# TTGO-TS-dash-display.net
KiCad netlist of a schematic drawn in EAGLE
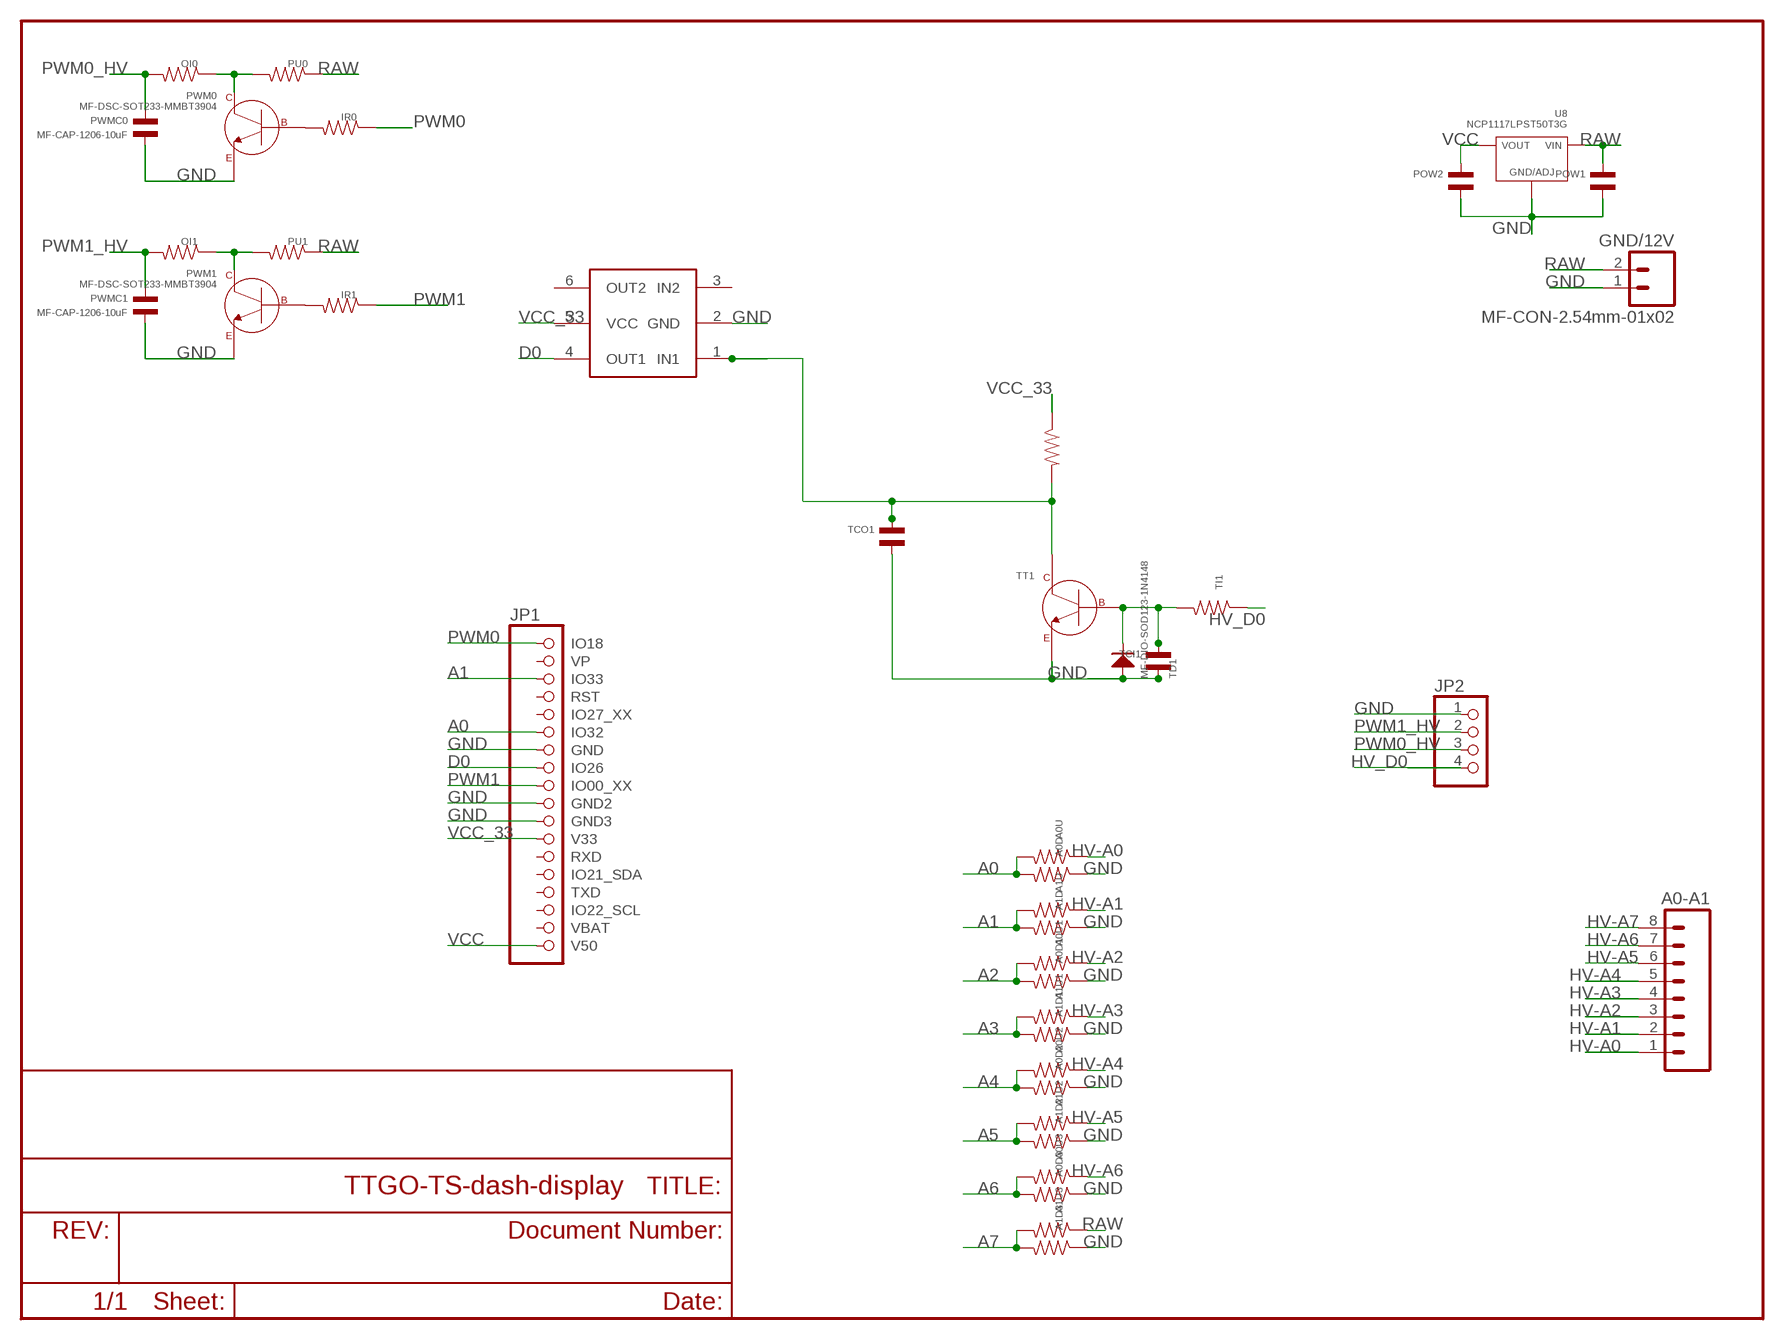
[diagram p0: schematic, sheet 1]

(export (version "E")
  (design (tool "Eeschema 10.0.6"))
  (components
    (comp (ref "A0-A1")
      (value "MF-CON-2.54mm-01x08")
      (footprint "eagle-import:1X08")
      (libsource (lib "eagle-import") (part "M081X08"))
    )
    (comp (ref "A0D")
      (value "RESISTOR_1206")
      (footprint "eagle-import:R1206")
      (libsource (lib "eagle-import") (part "RESISTOR_1206"))
    )
    (comp (ref "A0D1")
      (value "RESISTOR_1206")
      (footprint "eagle-import:R1206")
      (libsource (lib "eagle-import") (part "RESISTOR_1206"))
    )
    (comp (ref "A0D2")
      (value "RESISTOR_1206")
      (footprint "eagle-import:R1206")
      (libsource (lib "eagle-import") (part "RESISTOR_1206"))
    )
    (comp (ref "A0D3")
      (value "RESISTOR_1206")
      (footprint "eagle-import:R1206")
      (libsource (lib "eagle-import") (part "RESISTOR_1206"))
    )
    (comp (ref "A0U")
      (value "RESISTOR_1206")
      (footprint "eagle-import:R1206")
      (libsource (lib "eagle-import") (part "RESISTOR_1206"))
    )
    (comp (ref "A0U1")
      (value "RESISTOR_1206")
      (footprint "eagle-import:R1206")
      (libsource (lib "eagle-import") (part "RESISTOR_1206"))
    )
    (comp (ref "A0U2")
      (value "RESISTOR_1206")
      (footprint "eagle-import:R1206")
      (libsource (lib "eagle-import") (part "RESISTOR_1206"))
    )
    (comp (ref "A0U3")
      (value "RESISTOR_1206")
      (footprint "eagle-import:R1206")
      (libsource (lib "eagle-import") (part "RESISTOR_1206"))
    )
    (comp (ref "A1D")
      (value "RESISTOR_1206")
      (footprint "eagle-import:R1206")
      (libsource (lib "eagle-import") (part "RESISTOR_1206"))
    )
    (comp (ref "A1D1")
      (value "RESISTOR_1206")
      (footprint "eagle-import:R1206")
      (libsource (lib "eagle-import") (part "RESISTOR_1206"))
    )
    (comp (ref "A1D2")
      (value "RESISTOR_1206")
      (footprint "eagle-import:R1206")
      (libsource (lib "eagle-import") (part "RESISTOR_1206"))
    )
    (comp (ref "A1D3")
      (value "RESISTOR_1206")
      (footprint "eagle-import:R1206")
      (libsource (lib "eagle-import") (part "RESISTOR_1206"))
    )
    (comp (ref "A1U")
      (value "RESISTOR_1206")
      (footprint "eagle-import:R1206")
      (libsource (lib "eagle-import") (part "RESISTOR_1206"))
    )
    (comp (ref "A1U1")
      (value "RESISTOR_1206")
      (footprint "eagle-import:R1206")
      (libsource (lib "eagle-import") (part "RESISTOR_1206"))
    )
    (comp (ref "A1U2")
      (value "RESISTOR_1206")
      (footprint "eagle-import:R1206")
      (libsource (lib "eagle-import") (part "RESISTOR_1206"))
    )
    (comp (ref "A1U3")
      (value "RESISTOR_1206")
      (footprint "eagle-import:R1206")
      (libsource (lib "eagle-import") (part "RESISTOR_1206"))
    )
    (comp (ref "GND/12V")
      (value "MF-CON-2.54mm-01x02")
      (footprint "eagle-import:1X02")
      (libsource (lib "eagle-import") (part "M02PTH"))
    )
    (comp (ref "IR0")
      (value "RESISTOR_1206")
      (footprint "eagle-import:R1206")
      (libsource (lib "eagle-import") (part "RESISTOR_1206"))
    )
    (comp (ref "IR1")
      (value "RESISTOR_1206")
      (footprint "eagle-import:R1206")
      (libsource (lib "eagle-import") (part "RESISTOR_1206"))
    )
    (comp (ref "JP1")
      (value "000_ESP32_D1MINI")
      (footprint "eagle-import:00_2X9")
      (libsource (lib "eagle-import") (part "000_ESP32_D1MINI"))
    )
    (comp (ref "JP2")
      (value "HEADER-1X4")
      (footprint "eagle-import:1X04_OVAL")
      (libsource (lib "eagle-import") (part "HEADER-1X4"))
    )
    (comp (ref "OI0")
      (value "RESISTOR_1206")
      (footprint "eagle-import:R1206")
      (libsource (lib "eagle-import") (part "RESISTOR_1206"))
    )
    (comp (ref "OI1")
      (value "RESISTOR_1206")
      (footprint "eagle-import:R1206")
      (libsource (lib "eagle-import") (part "RESISTOR_1206"))
    )
    (comp (ref "POW1")
      (value "CAPACITOR_NP_1210")
      (footprint "eagle-import:C1210")
      (libsource (lib "eagle-import") (part "CAPACITOR_NP_1210"))
    )
    (comp (ref "POW2")
      (value "CAPACITOR_NP_1210")
      (footprint "eagle-import:C1210")
      (libsource (lib "eagle-import") (part "CAPACITOR_NP_1210"))
    )
    (comp (ref "PU0")
      (value "RESISTOR_1206")
      (footprint "eagle-import:R1206")
      (libsource (lib "eagle-import") (part "RESISTOR_1206"))
    )
    (comp (ref "PU1")
      (value "RESISTOR_1206")
      (footprint "eagle-import:R1206")
      (libsource (lib "eagle-import") (part "RESISTOR_1206"))
    )
    (comp (ref "PWM0")
      (value "MF-DSC-SOT233-MMBT3904")
      (footprint "eagle-import:SOT-23-3")
      (fields (field (name "HOUSEPART") "YES"))
      (libsource (lib "eagle-import") (part "NPN_BJT_SOT-23-3MMBT3904"))
    )
    (comp (ref "PWM1")
      (value "MF-DSC-SOT233-MMBT3904")
      (footprint "eagle-import:SOT-23-3")
      (fields (field (name "HOUSEPART") "YES"))
      (libsource (lib "eagle-import") (part "NPN_BJT_SOT-23-3MMBT3904"))
    )
    (comp (ref "PWMC0")
      (value "MF-CAP-1206-10uF")
      (footprint "eagle-import:C1206")
      (libsource (lib "eagle-import") (part "CAPACITOR_NP_1206"))
    )
    (comp (ref "PWMC1")
      (value "MF-CAP-1206-10uF")
      (footprint "eagle-import:C1206")
      (libsource (lib "eagle-import") (part "CAPACITOR_NP_1206"))
    )
    (comp (ref "TCI1")
      (value "CAPACITOR_NP_1210")
      (footprint "eagle-import:C1210")
      (libsource (lib "eagle-import") (part "CAPACITOR_NP_1210"))
    )
    (comp (ref "TCO1")
      (value "CAPACITOR_NP_1210")
      (footprint "eagle-import:C1210")
      (libsource (lib "eagle-import") (part "CAPACITOR_NP_1210"))
    )
    (comp (ref "TD1")
      (value "MF-DIO-SOD123-1N4148")
      (footprint "eagle-import:SOD-123")
      (fields (field (name "HOUSEPART") "YES"))
      (libsource (lib "eagle-import") (part "DIODES_SOD-123_1N4148"))
    )
    (comp (ref "TI1")
      (value "RESISTOR_1206")
      (footprint "eagle-import:R1206")
      (libsource (lib "eagle-import") (part "RESISTOR_1206"))
    )
    (comp (ref "TT1")
      (value "MF-DSC-SOT233-MMBT3904")
      (footprint "eagle-import:SOT-23-3")
      (fields (field (name "HOUSEPART") "YES"))
      (libsource (lib "eagle-import") (part "NPN_BJT_SOT-23-3MMBT3904"))
    )
    (comp (ref "TU1")
      (value "RESISTOR_1206")
      (footprint "eagle-import:R1206")
      (libsource (lib "eagle-import") (part "RESISTOR_1206"))
    )
    (comp (ref "U$1")
      (value "000_DUAL-SCHMITT-INVERTER")
      (footprint "eagle-import:SOT23-6")
      (libsource (lib "eagle-import") (part "000_DUAL-SCHMITT-INVERTER"))
    )
    (comp (ref "U8")
      (value "NCP1117LPST50T3G")
      (footprint "eagle-import:SOT-223-3")
      (fields (field (name "HOUSEPART") "NO"))
      (libsource (lib "eagle-import") (part "NCP1117LPST50T3G"))
    )
  )
  (nets
    (net (code "1") (name "/A0") (class "Default")
      (node (ref "A0D") (pin "P$2") (pinfunction "P$2_P$2") (pintype "passive"))
      (node (ref "A0U") (pin "P$2") (pinfunction "P$2_P$2") (pintype "passive"))
      (node (ref "JP1") (pin "6") (pinfunction "IO32_6") (pintype "passive"))
    )
    (net (code "2") (name "/A1") (class "Default")
      (node (ref "A1D") (pin "P$2") (pinfunction "P$2_P$2") (pintype "passive"))
      (node (ref "A1U") (pin "P$2") (pinfunction "P$2_P$2") (pintype "passive"))
      (node (ref "JP1") (pin "3") (pinfunction "IO33_3") (pintype "passive"))
    )
    (net (code "3") (name "/A2") (class "Default")
      (node (ref "A0D1") (pin "P$2") (pinfunction "P$2_P$2") (pintype "passive"))
      (node (ref "A0U1") (pin "P$2") (pinfunction "P$2_P$2") (pintype "passive"))
    )
    (net (code "4") (name "/A3") (class "Default")
      (node (ref "A1D1") (pin "P$2") (pinfunction "P$2_P$2") (pintype "passive"))
      (node (ref "A1U1") (pin "P$2") (pinfunction "P$2_P$2") (pintype "passive"))
    )
    (net (code "5") (name "/A4") (class "Default")
      (node (ref "A0D2") (pin "P$2") (pinfunction "P$2_P$2") (pintype "passive"))
      (node (ref "A0U2") (pin "P$2") (pinfunction "P$2_P$2") (pintype "passive"))
    )
    (net (code "6") (name "/A5") (class "Default")
      (node (ref "A1D2") (pin "P$2") (pinfunction "P$2_P$2") (pintype "passive"))
      (node (ref "A1U2") (pin "P$2") (pinfunction "P$2_P$2") (pintype "passive"))
    )
    (net (code "7") (name "/A6") (class "Default")
      (node (ref "A0D3") (pin "P$2") (pinfunction "P$2_P$2") (pintype "passive"))
      (node (ref "A0U3") (pin "P$2") (pinfunction "P$2_P$2") (pintype "passive"))
    )
    (net (code "8") (name "/A7") (class "Default")
      (node (ref "A1D3") (pin "P$2") (pinfunction "P$2_P$2") (pintype "passive"))
      (node (ref "A1U3") (pin "P$2") (pinfunction "P$2_P$2") (pintype "passive"))
    )
    (net (code "9") (name "/D0") (class "Default")
      (node (ref "JP1") (pin "8") (pinfunction "IO26_8") (pintype "passive"))
      (node (ref "U$1") (pin "4") (pinfunction "OUT1_4") (pintype "bidirectional"))
    )
    (net (code "10") (name "/GND") (class "Default")
      (node (ref "A0D") (pin "P$1") (pinfunction "P$1_P$1") (pintype "passive"))
      (node (ref "A0D1") (pin "P$1") (pinfunction "P$1_P$1") (pintype "passive"))
      (node (ref "A0D2") (pin "P$1") (pinfunction "P$1_P$1") (pintype "passive"))
      (node (ref "A0D3") (pin "P$1") (pinfunction "P$1_P$1") (pintype "passive"))
      (node (ref "A1D") (pin "P$1") (pinfunction "P$1_P$1") (pintype "passive"))
      (node (ref "A1D1") (pin "P$1") (pinfunction "P$1_P$1") (pintype "passive"))
      (node (ref "A1D2") (pin "P$1") (pinfunction "P$1_P$1") (pintype "passive"))
      (node (ref "A1D3") (pin "P$1") (pinfunction "P$1_P$1") (pintype "passive"))
      (node (ref "GND/12V") (pin "1") (pinfunction "1_1") (pintype "passive"))
      (node (ref "JP1") (pin "10") (pinfunction "GND2_10") (pintype "power_in"))
      (node (ref "JP1") (pin "11") (pinfunction "GND3_11") (pintype "power_in"))
      (node (ref "JP1") (pin "7") (pinfunction "GND_7") (pintype "power_in"))
      (node (ref "JP2") (pin "1") (pinfunction "1_1") (pintype "passive"))
      (node (ref "POW1") (pin "P$2") (pinfunction "P$2_P$2") (pintype "passive"))
      (node (ref "POW2") (pin "P$2") (pinfunction "P$2_P$2") (pintype "passive"))
      (node (ref "PWM0") (pin "P$2") (pinfunction "EMITTER_P$2") (pintype "bidirectional"))
      (node (ref "PWM1") (pin "P$2") (pinfunction "EMITTER_P$2") (pintype "bidirectional"))
      (node (ref "PWMC0") (pin "P$2") (pinfunction "P$2_P$2") (pintype "passive"))
      (node (ref "PWMC1") (pin "P$2") (pinfunction "P$2_P$2") (pintype "passive"))
      (node (ref "TCI1") (pin "P$2") (pinfunction "P$2_P$2") (pintype "passive"))
      (node (ref "TCO1") (pin "P$2") (pinfunction "P$2_P$2") (pintype "passive"))
      (node (ref "TD1") (pin "ANODE") (pinfunction "ANODE_ANODE") (pintype "bidirectional"))
      (node (ref "TT1") (pin "P$2") (pinfunction "EMITTER_P$2") (pintype "bidirectional"))
      (node (ref "U$1") (pin "2") (pinfunction "GND_2") (pintype "bidirectional"))
      (node (ref "U8") (pin "P$2") (pinfunction "GND/ADJ_P$2") (pintype "bidirectional"))
    )
    (net (code "11") (name "/HV-A0") (class "Default")
      (node (ref "A0-A1") (pin "1") (pinfunction "1_1") (pintype "passive"))
      (node (ref "A0U") (pin "P$1") (pinfunction "P$1_P$1") (pintype "passive"))
    )
    (net (code "12") (name "/HV-A1") (class "Default")
      (node (ref "A0-A1") (pin "2") (pinfunction "2_2") (pintype "passive"))
      (node (ref "A1U") (pin "P$1") (pinfunction "P$1_P$1") (pintype "passive"))
    )
    (net (code "13") (name "/HV-A2") (class "Default")
      (node (ref "A0-A1") (pin "3") (pinfunction "3_3") (pintype "passive"))
      (node (ref "A0U1") (pin "P$1") (pinfunction "P$1_P$1") (pintype "passive"))
    )
    (net (code "14") (name "/HV-A3") (class "Default")
      (node (ref "A0-A1") (pin "4") (pinfunction "4_4") (pintype "passive"))
      (node (ref "A1U1") (pin "P$1") (pinfunction "P$1_P$1") (pintype "passive"))
    )
    (net (code "15") (name "/HV-A4") (class "Default")
      (node (ref "A0-A1") (pin "5") (pinfunction "5_5") (pintype "passive"))
      (node (ref "A0U2") (pin "P$1") (pinfunction "P$1_P$1") (pintype "passive"))
    )
    (net (code "16") (name "/HV-A5") (class "Default")
      (node (ref "A0-A1") (pin "6") (pinfunction "6_6") (pintype "passive"))
      (node (ref "A1U2") (pin "P$1") (pinfunction "P$1_P$1") (pintype "passive"))
    )
    (net (code "17") (name "/HV-A6") (class "Default")
      (node (ref "A0-A1") (pin "7") (pinfunction "7_7") (pintype "passive"))
      (node (ref "A0U3") (pin "P$1") (pinfunction "P$1_P$1") (pintype "passive"))
    )
    (net (code "18") (name "/HV-A7") (class "Default")
      (node (ref "A0-A1") (pin "8") (pinfunction "8_8") (pintype "passive"))
    )
    (net (code "19") (name "/HV_D0") (class "Default")
      (node (ref "JP2") (pin "4") (pinfunction "4_4") (pintype "passive"))
      (node (ref "TI1") (pin "P$1") (pinfunction "P$1_P$1") (pintype "passive"))
    )
    (net (code "20") (name "/PWM0") (class "Default")
      (node (ref "IR0") (pin "P$1") (pinfunction "P$1_P$1") (pintype "passive"))
      (node (ref "JP1") (pin "1") (pinfunction "IO18_1") (pintype "passive"))
    )
    (net (code "21") (name "/PWM0_HV") (class "Default")
      (node (ref "JP2") (pin "3") (pinfunction "3_3") (pintype "passive"))
      (node (ref "OI0") (pin "P$2") (pinfunction "P$2_P$2") (pintype "passive"))
      (node (ref "PWMC0") (pin "P$1") (pinfunction "P$1_P$1") (pintype "passive"))
    )
    (net (code "22") (name "/PWM1") (class "Default")
      (node (ref "IR1") (pin "P$1") (pinfunction "P$1_P$1") (pintype "passive"))
      (node (ref "JP1") (pin "9") (pinfunction "IO00_XX_9") (pintype "passive"))
    )
    (net (code "23") (name "/PWM1_HV") (class "Default")
      (node (ref "JP2") (pin "2") (pinfunction "2_2") (pintype "passive"))
      (node (ref "OI1") (pin "P$2") (pinfunction "P$2_P$2") (pintype "passive"))
      (node (ref "PWMC1") (pin "P$1") (pinfunction "P$1_P$1") (pintype "passive"))
    )
    (net (code "24") (name "/RAW") (class "Default")
      (node (ref "A1U3") (pin "P$1") (pinfunction "P$1_P$1") (pintype "passive"))
      (node (ref "GND/12V") (pin "2") (pinfunction "2_2") (pintype "passive"))
      (node (ref "POW1") (pin "P$1") (pinfunction "P$1_P$1") (pintype "passive"))
      (node (ref "PU0") (pin "P$1") (pinfunction "P$1_P$1") (pintype "passive"))
      (node (ref "PU1") (pin "P$1") (pinfunction "P$1_P$1") (pintype "passive"))
      (node (ref "U8") (pin "P$4") (pinfunction "VIN_P$4") (pintype "bidirectional"))
    )
    (net (code "25") (name "/VCC") (class "Default")
      (node (ref "JP1") (pin "18") (pinfunction "V50_18") (pintype "power_in"))
      (node (ref "POW2") (pin "P$1") (pinfunction "P$1_P$1") (pintype "passive"))
      (node (ref "U8") (pin "P$1") (pinfunction "VOUT_P$1") (pintype "bidirectional"))
      (node (ref "U8") (pin "P$3") (pinfunction "VOUT_P$3") (pintype "bidirectional"))
    )
    (net (code "26") (name "/VCC_33") (class "Default")
      (node (ref "JP1") (pin "12") (pinfunction "V33_12") (pintype "passive"))
      (node (ref "TU1") (pin "P$1") (pinfunction "P$1_P$1") (pintype "passive"))
      (node (ref "U$1") (pin "5") (pinfunction "VCC_5") (pintype "bidirectional"))
    )
    (net (code "27") (name "Net-(PWM0-BASE)") (class "Default")
      (node (ref "IR0") (pin "P$2") (pinfunction "P$2_P$2") (pintype "passive"))
      (node (ref "PWM0") (pin "P$1") (pinfunction "BASE_P$1") (pintype "bidirectional"))
    )
    (net (code "28") (name "Net-(PWM0-COLLECTOR)") (class "Default")
      (node (ref "OI0") (pin "P$1") (pinfunction "P$1_P$1") (pintype "passive"))
      (node (ref "PU0") (pin "P$2") (pinfunction "P$2_P$2") (pintype "passive"))
      (node (ref "PWM0") (pin "P$3") (pinfunction "COLLECTOR_P$3") (pintype "bidirectional"))
    )
    (net (code "29") (name "Net-(PWM1-BASE)") (class "Default")
      (node (ref "IR1") (pin "P$2") (pinfunction "P$2_P$2") (pintype "passive"))
      (node (ref "PWM1") (pin "P$1") (pinfunction "BASE_P$1") (pintype "bidirectional"))
    )
    (net (code "30") (name "Net-(PWM1-COLLECTOR)") (class "Default")
      (node (ref "OI1") (pin "P$1") (pinfunction "P$1_P$1") (pintype "passive"))
      (node (ref "PU1") (pin "P$2") (pinfunction "P$2_P$2") (pintype "passive"))
      (node (ref "PWM1") (pin "P$3") (pinfunction "COLLECTOR_P$3") (pintype "bidirectional"))
    )
    (net (code "31") (name "Net-(TT1-BASE)") (class "Default")
      (node (ref "TCI1") (pin "P$1") (pinfunction "P$1_P$1") (pintype "passive"))
      (node (ref "TD1") (pin "CATHODE") (pinfunction "CATHODE_CATHODE") (pintype "bidirectional"))
      (node (ref "TI1") (pin "P$2") (pinfunction "P$2_P$2") (pintype "passive"))
      (node (ref "TT1") (pin "P$1") (pinfunction "BASE_P$1") (pintype "bidirectional"))
    )
    (net (code "32") (name "Net-(TT1-COLLECTOR)") (class "Default")
      (node (ref "TCO1") (pin "P$1") (pinfunction "P$1_P$1") (pintype "passive"))
      (node (ref "TT1") (pin "P$3") (pinfunction "COLLECTOR_P$3") (pintype "bidirectional"))
      (node (ref "TU1") (pin "P$2") (pinfunction "P$2_P$2") (pintype "passive"))
      (node (ref "U$1") (pin "1") (pinfunction "IN1_1") (pintype "bidirectional"))
    )
    (net (code "33") (name "unconnected-(JP1-IO21_SDA-Pad14)") (class "Default")
      (node (ref "JP1") (pin "14") (pinfunction "IO21_SDA_14") (pintype "passive"))
    )
    (net (code "34") (name "unconnected-(JP1-IO22_SCL-Pad16)") (class "Default")
      (node (ref "JP1") (pin "16") (pinfunction "IO22_SCL_16") (pintype "passive"))
    )
    (net (code "35") (name "unconnected-(JP1-IO27_XX-Pad5)") (class "Default")
      (node (ref "JP1") (pin "5") (pinfunction "IO27_XX_5") (pintype "passive"))
    )
    (net (code "36") (name "unconnected-(JP1-RST-Pad4)") (class "Default")
      (node (ref "JP1") (pin "4") (pinfunction "RST_4") (pintype "passive"))
    )
    (net (code "37") (name "unconnected-(JP1-RXD-Pad13)") (class "Default")
      (node (ref "JP1") (pin "13") (pinfunction "RXD_13") (pintype "passive"))
    )
    (net (code "38") (name "unconnected-(JP1-TXD-Pad15)") (class "Default")
      (node (ref "JP1") (pin "15") (pinfunction "TXD_15") (pintype "passive"))
    )
    (net (code "39") (name "unconnected-(JP1-VBAT-Pad17)") (class "Default")
      (node (ref "JP1") (pin "17") (pinfunction "VBAT_17") (pintype "passive"))
    )
    (net (code "40") (name "unconnected-(JP1-VP-Pad2)") (class "Default")
      (node (ref "JP1") (pin "2") (pinfunction "VP_2") (pintype "passive"))
    )
    (net (code "41") (name "unconnected-(U$1-IN2-Pad3)") (class "Default")
      (node (ref "U$1") (pin "3") (pinfunction "IN2_3") (pintype "bidirectional"))
    )
    (net (code "42") (name "unconnected-(U$1-OUT2-Pad6)") (class "Default")
      (node (ref "U$1") (pin "6") (pinfunction "OUT2_6") (pintype "bidirectional"))
    )
  )
)
